# MEMSAndAnalogFrontend.net
KiCad netlist of a schematic drawn in Altium Designer
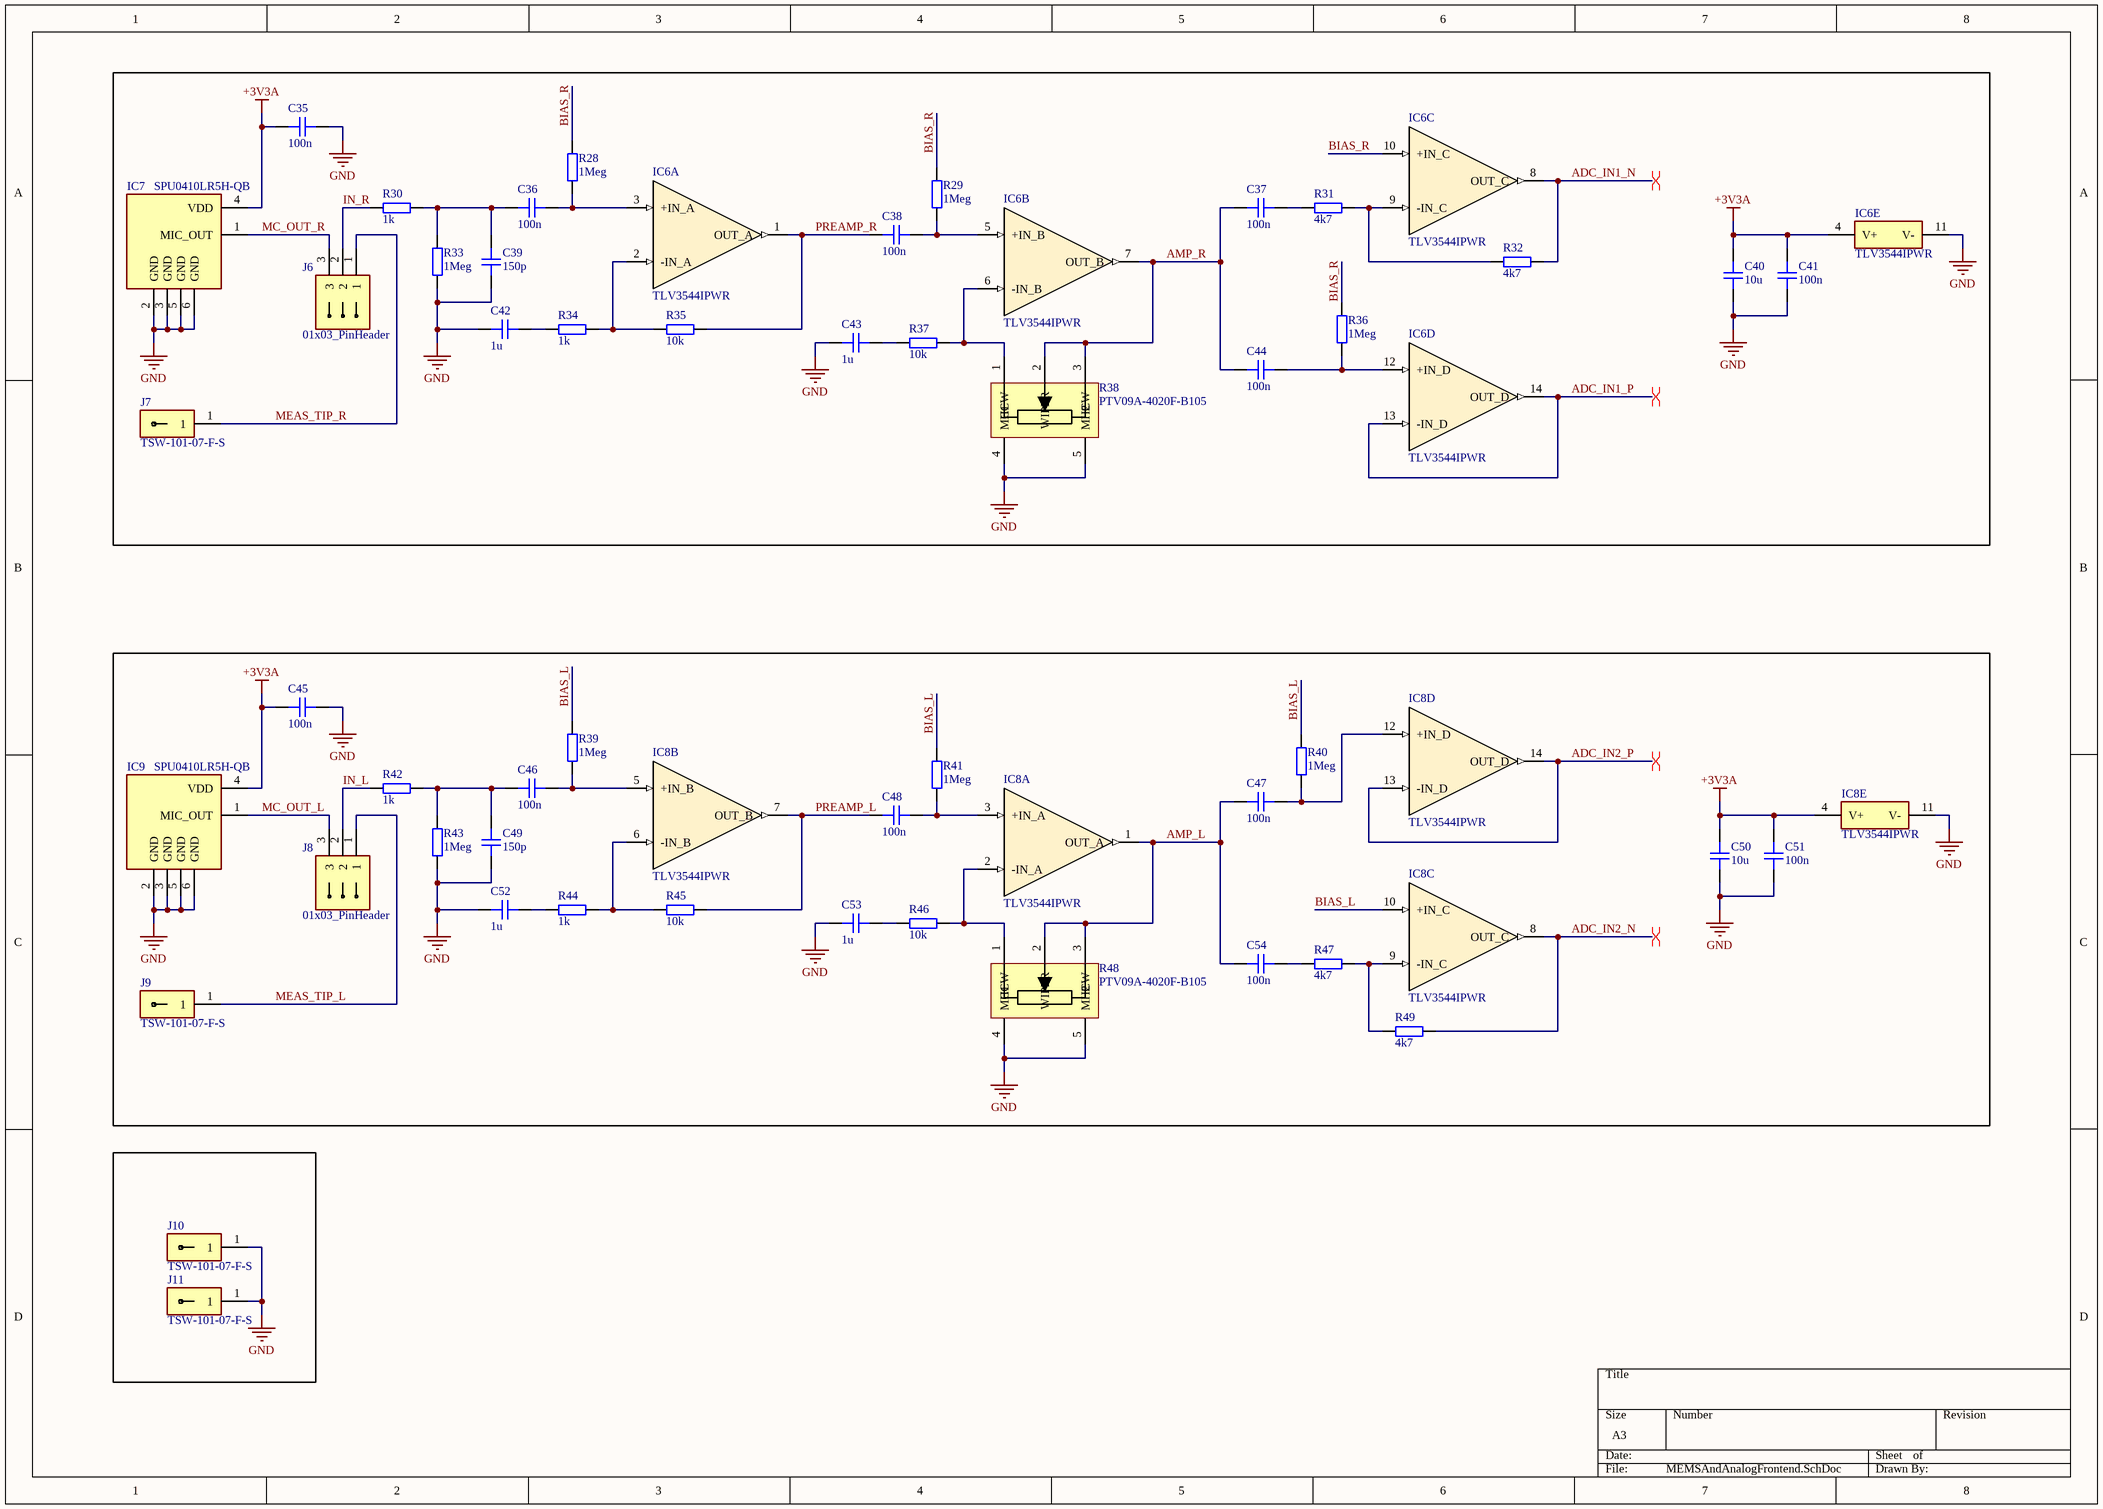
[diagram p0: MEMSAndAnalogFrontend.SchDoc]

(export (version "E")
  (design (tool "Eeschema 10.0.6"))
  (components
    (comp (ref "C35")
      (value "100n")
      (footprint "CAP_0402")
      (description "Capacitor SMD 0402")
      (libsource (lib "Schematic-Lib-PhilsLab") (part "CAP_0402"))
    )
    (comp (ref "C36")
      (value "100n")
      (footprint "CAP_0402")
      (description "Capacitor SMD 0402")
      (libsource (lib "Schematic-Lib-PhilsLab") (part "CAP_0402"))
    )
    (comp (ref "C37")
      (value "100n")
      (footprint "CAP_0402")
      (description "Capacitor SMD 0402")
      (libsource (lib "Schematic-Lib-PhilsLab") (part "CAP_0402"))
    )
    (comp (ref "C38")
      (value "100n")
      (footprint "CAP_0402")
      (description "Capacitor SMD 0402")
      (libsource (lib "Schematic-Lib-PhilsLab") (part "CAP_0402"))
    )
    (comp (ref "C39")
      (value "150p")
      (footprint "CAP_0402")
      (description "Capacitor SMD 0402")
      (libsource (lib "Schematic-Lib-PhilsLab") (part "CAP_0402"))
    )
    (comp (ref "C40")
      (value "10u")
      (footprint "CAP_0603")
      (description "Capacitor SMD 0603")
      (libsource (lib "Schematic-Lib-PhilsLab") (part "CAP_0603"))
    )
    (comp (ref "C41")
      (value "100n")
      (footprint "CAP_0402")
      (description "Capacitor SMD 0402")
      (libsource (lib "Schematic-Lib-PhilsLab") (part "CAP_0402"))
    )
    (comp (ref "C42")
      (value "1u")
      (footprint "CAP_0402")
      (description "Capacitor SMD 0402")
      (libsource (lib "Schematic-Lib-PhilsLab") (part "CAP_0402"))
    )
    (comp (ref "C43")
      (value "1u")
      (footprint "CAP_0402")
      (description "Capacitor SMD 0402")
      (libsource (lib "Schematic-Lib-PhilsLab") (part "CAP_0402"))
    )
    (comp (ref "C44")
      (value "100n")
      (footprint "CAP_0402")
      (description "Capacitor SMD 0402")
      (libsource (lib "Schematic-Lib-PhilsLab") (part "CAP_0402"))
    )
    (comp (ref "C45")
      (value "100n")
      (footprint "CAP_0402")
      (description "Capacitor SMD 0402")
      (libsource (lib "Schematic-Lib-PhilsLab") (part "CAP_0402"))
    )
    (comp (ref "C46")
      (value "100n")
      (footprint "CAP_0402")
      (description "Capacitor SMD 0402")
      (libsource (lib "Schematic-Lib-PhilsLab") (part "CAP_0402"))
    )
    (comp (ref "C47")
      (value "100n")
      (footprint "CAP_0402")
      (description "Capacitor SMD 0402")
      (libsource (lib "Schematic-Lib-PhilsLab") (part "CAP_0402"))
    )
    (comp (ref "C48")
      (value "100n")
      (footprint "CAP_0402")
      (description "Capacitor SMD 0402")
      (libsource (lib "Schematic-Lib-PhilsLab") (part "CAP_0402"))
    )
    (comp (ref "C49")
      (value "150p")
      (footprint "CAP_0402")
      (description "Capacitor SMD 0402")
      (libsource (lib "Schematic-Lib-PhilsLab") (part "CAP_0402"))
    )
    (comp (ref "C50")
      (value "10u")
      (footprint "CAP_0603")
      (description "Capacitor SMD 0603")
      (libsource (lib "Schematic-Lib-PhilsLab") (part "CAP_0603"))
    )
    (comp (ref "C51")
      (value "100n")
      (footprint "CAP_0402")
      (description "Capacitor SMD 0402")
      (libsource (lib "Schematic-Lib-PhilsLab") (part "CAP_0402"))
    )
    (comp (ref "C52")
      (value "1u")
      (footprint "CAP_0402")
      (description "Capacitor SMD 0402")
      (libsource (lib "Schematic-Lib-PhilsLab") (part "CAP_0402"))
    )
    (comp (ref "C53")
      (value "1u")
      (footprint "CAP_0402")
      (description "Capacitor SMD 0402")
      (libsource (lib "Schematic-Lib-PhilsLab") (part "CAP_0402"))
    )
    (comp (ref "C54")
      (value "100n")
      (footprint "CAP_0402")
      (description "Capacitor SMD 0402")
      (libsource (lib "Schematic-Lib-PhilsLab") (part "CAP_0402"))
    )
    (comp (ref "IC6")
      (value "TLV3544IPWR")
      (footprint "BAT_Detector_PCBLib:SOP65P640X120-14N")
      (description "Integrated Circuit")
      (fields (field (name "MOUSER PART NUMBER") "595-TLV3544IPWR"))
      (libsource (lib "BAT_Detector_SCHLib") (part "TLV3544IPWR"))
    )
    (comp (ref "IC7")
      (value "SPU0410LR5H-QB")
      (footprint "SPU0410LR5H-QB")
      (description "Knowles - MEMS Microphones MIC MEMS ANALOG OMNI -38DB")
      (libsource (lib "BAT_Detector_SCHLib") (part "SPU0410LR5H-QB"))
    )
    (comp (ref "IC8")
      (value "TLV3544IPWR")
      (footprint "BAT_Detector_PCBLib:SOP65P640X120-14N")
      (description "Integrated Circuit")
      (fields (field (name "MOUSER PART NUMBER") "595-TLV3544IPWR"))
      (libsource (lib "BAT_Detector_SCHLib") (part "TLV3544IPWR"))
    )
    (comp (ref "IC9")
      (value "SPU0410LR5H-QB")
      (footprint "SPU0410LR5H-QB")
      (description "Knowles - MEMS Microphones MIC MEMS ANALOG OMNI -38DB")
      (libsource (lib "BAT_Detector_SCHLib") (part "SPU0410LR5H-QB"))
    )
    (comp (ref "J6")
      (value "01x03_PinHeader")
      (footprint "BAT_Detector_PCBLib:HDRV3W64P0X254_1X3_732X244X854P")
      (description "Connector")
      (fields
        (field (name "MANUFACTURER_PART_NUMBER") "A2-3PA-2.54DSA(71)")
        (field (name "MOUSER PART NUMBER") "798-A23PA254DSA71")
      )
      (libsource (lib "BAT_Detector_SCHLib") (part "01x03_PinHeader"))
    )
    (comp (ref "J7")
      (value "TSW-101-07-F-S")
      (footprint "BAT_Detector_PCBLib:TSW-101-XX-YY-S")
      (description "Connector")
      (fields (field (name "MOUSER PART NUMBER") "200-TSW10107FS"))
      (libsource (lib "BAT_Detector_SCHLib") (part "TSW-101-07-F-S"))
    )
    (comp (ref "J8")
      (value "01x03_PinHeader")
      (footprint "BAT_Detector_PCBLib:HDRV3W64P0X254_1X3_732X244X854P")
      (description "Connector")
      (fields
        (field (name "MANUFACTURER_PART_NUMBER") "A2-3PA-2.54DSA(71)")
        (field (name "MOUSER PART NUMBER") "798-A23PA254DSA71")
      )
      (libsource (lib "BAT_Detector_SCHLib") (part "01x03_PinHeader"))
    )
    (comp (ref "J9")
      (value "TSW-101-07-F-S")
      (footprint "BAT_Detector_PCBLib:TSW-101-XX-YY-S")
      (description "Connector")
      (fields (field (name "MOUSER PART NUMBER") "200-TSW10107FS"))
      (libsource (lib "BAT_Detector_SCHLib") (part "TSW-101-07-F-S"))
    )
    (comp (ref "J10")
      (value "TSW-101-07-F-S")
      (footprint "BAT_Detector_PCBLib:TSW-101-XX-YY-S")
      (description "Connector")
      (fields (field (name "MOUSER PART NUMBER") "200-TSW10107FS"))
      (libsource (lib "BAT_Detector_SCHLib") (part "TSW-101-07-F-S"))
    )
    (comp (ref "J11")
      (value "TSW-101-07-F-S")
      (footprint "BAT_Detector_PCBLib:TSW-101-XX-YY-S")
      (description "Connector")
      (fields (field (name "MOUSER PART NUMBER") "200-TSW10107FS"))
      (libsource (lib "BAT_Detector_SCHLib") (part "TSW-101-07-F-S"))
    )
    (comp (ref "R28")
      (value "1Meg")
      (footprint "RES_0402")
      (description "Resistor SMD 0402")
      (libsource (lib "Schematic-Lib-PhilsLab") (part "RES_0402"))
    )
    (comp (ref "R29")
      (value "1Meg")
      (footprint "RES_0402")
      (description "Resistor SMD 0402")
      (libsource (lib "Schematic-Lib-PhilsLab") (part "RES_0402"))
    )
    (comp (ref "R30")
      (value "1k")
      (footprint "RES_0402")
      (description "Resistor SMD 0402")
      (libsource (lib "Schematic-Lib-PhilsLab") (part "RES_0402"))
    )
    (comp (ref "R31")
      (value "4k7")
      (footprint "RES_0402")
      (description "Resistor SMD 0402")
      (libsource (lib "Schematic-Lib-PhilsLab") (part "RES_0402"))
    )
    (comp (ref "R32")
      (value "4k7")
      (footprint "RES_0402")
      (description "Resistor SMD 0402")
      (libsource (lib "Schematic-Lib-PhilsLab") (part "RES_0402"))
    )
    (comp (ref "R33")
      (value "1Meg")
      (footprint "RES_0402")
      (description "Resistor SMD 0402")
      (libsource (lib "Schematic-Lib-PhilsLab") (part "RES_0402"))
    )
    (comp (ref "R34")
      (value "1k")
      (footprint "RES_0402")
      (description "Resistor SMD 0402")
      (libsource (lib "Schematic-Lib-PhilsLab") (part "RES_0402"))
    )
    (comp (ref "R35")
      (value "10k")
      (footprint "RES_0402")
      (description "Resistor SMD 0402")
      (libsource (lib "Schematic-Lib-PhilsLab") (part "RES_0402"))
    )
    (comp (ref "R36")
      (value "1Meg")
      (footprint "RES_0402")
      (description "Resistor SMD 0402")
      (libsource (lib "Schematic-Lib-PhilsLab") (part "RES_0402"))
    )
    (comp (ref "R37")
      (value "10k")
      (footprint "RES_0402")
      (description "Resistor SMD 0402")
      (libsource (lib "Schematic-Lib-PhilsLab") (part "RES_0402"))
    )
    (comp (ref "R38")
      (value "PTV09A-4020F-B105")
      (footprint "BAT_Detector_PCBLib:PTV09A4020FB103")
      (description "Variable Resistor")
      (fields (field (name "MOUSER PART NUMBER") "652-PTV09A4020FB105"))
      (libsource (lib "BAT_Detector_SCHLib") (part "PTV09A-4020F-B105"))
    )
    (comp (ref "R39")
      (value "1Meg")
      (footprint "RES_0402")
      (description "Resistor SMD 0402")
      (libsource (lib "Schematic-Lib-PhilsLab") (part "RES_0402"))
    )
    (comp (ref "R40")
      (value "1Meg")
      (footprint "RES_0402")
      (description "Resistor SMD 0402")
      (libsource (lib "Schematic-Lib-PhilsLab") (part "RES_0402"))
    )
    (comp (ref "R41")
      (value "1Meg")
      (footprint "RES_0402")
      (description "Resistor SMD 0402")
      (libsource (lib "Schematic-Lib-PhilsLab") (part "RES_0402"))
    )
    (comp (ref "R42")
      (value "1k")
      (footprint "RES_0402")
      (description "Resistor SMD 0402")
      (libsource (lib "Schematic-Lib-PhilsLab") (part "RES_0402"))
    )
    (comp (ref "R43")
      (value "1Meg")
      (footprint "RES_0402")
      (description "Resistor SMD 0402")
      (libsource (lib "Schematic-Lib-PhilsLab") (part "RES_0402"))
    )
    (comp (ref "R44")
      (value "1k")
      (footprint "RES_0402")
      (description "Resistor SMD 0402")
      (libsource (lib "Schematic-Lib-PhilsLab") (part "RES_0402"))
    )
    (comp (ref "R45")
      (value "10k")
      (footprint "RES_0402")
      (description "Resistor SMD 0402")
      (libsource (lib "Schematic-Lib-PhilsLab") (part "RES_0402"))
    )
    (comp (ref "R46")
      (value "10k")
      (footprint "RES_0402")
      (description "Resistor SMD 0402")
      (libsource (lib "Schematic-Lib-PhilsLab") (part "RES_0402"))
    )
    (comp (ref "R47")
      (value "4k7")
      (footprint "RES_0402")
      (description "Resistor SMD 0402")
      (libsource (lib "Schematic-Lib-PhilsLab") (part "RES_0402"))
    )
    (comp (ref "R48")
      (value "PTV09A-4020F-B105")
      (footprint "BAT_Detector_PCBLib:PTV09A4020FB103")
      (description "Variable Resistor")
      (fields (field (name "MOUSER PART NUMBER") "652-PTV09A4020FB105"))
      (libsource (lib "BAT_Detector_SCHLib") (part "PTV09A-4020F-B105"))
    )
    (comp (ref "R49")
      (value "4k7")
      (footprint "RES_0402")
      (description "Resistor SMD 0402")
      (libsource (lib "Schematic-Lib-PhilsLab") (part "RES_0402"))
    )
  )
  (nets
    (net (code "1") (name "+3V3A") (class "Default")
      (node (ref "C35") (pin "1") (pinfunction "1_1") (pintype "passive"))
      (node (ref "C40") (pin "2") (pinfunction "2_2") (pintype "passive"))
      (node (ref "C41") (pin "2") (pinfunction "2_2") (pintype "passive"))
      (node (ref "C45") (pin "1") (pinfunction "1_1") (pintype "passive"))
      (node (ref "C50") (pin "2") (pinfunction "2_2") (pintype "passive"))
      (node (ref "C51") (pin "2") (pinfunction "2_2") (pintype "passive"))
      (node (ref "IC6") (pin "4") (pinfunction "V+_4") (pintype "power_in"))
      (node (ref "IC7") (pin "4") (pinfunction "VDD_4") (pintype "passive"))
      (node (ref "IC8") (pin "4") (pinfunction "V+_4") (pintype "power_in"))
      (node (ref "IC9") (pin "4") (pinfunction "VDD_4") (pintype "passive"))
    )
    (net (code "2") (name "/ADC_IN1_N") (class "Default")
      (node (ref "IC6") (pin "8") (pinfunction "OUT_C_8") (pintype "output"))
      (node (ref "R32") (pin "2") (pinfunction "2_2") (pintype "passive"))
    )
    (net (code "3") (name "/ADC_IN1_P") (class "Default")
      (node (ref "IC6") (pin "13") (pinfunction "-IN_D_13") (pintype "input"))
      (node (ref "IC6") (pin "14") (pinfunction "OUT_D_14") (pintype "output"))
    )
    (net (code "4") (name "/ADC_IN2_N") (class "Default")
      (node (ref "IC8") (pin "8") (pinfunction "OUT_C_8") (pintype "output"))
      (node (ref "R49") (pin "2") (pinfunction "2_2") (pintype "passive"))
    )
    (net (code "5") (name "/ADC_IN2_P") (class "Default")
      (node (ref "IC8") (pin "13") (pinfunction "-IN_D_13") (pintype "input"))
      (node (ref "IC8") (pin "14") (pinfunction "OUT_D_14") (pintype "output"))
    )
    (net (code "6") (name "/AMP_L") (class "Default")
      (node (ref "C47") (pin "2") (pinfunction "2_2") (pintype "passive"))
      (node (ref "C54") (pin "2") (pinfunction "2_2") (pintype "passive"))
      (node (ref "IC8") (pin "1") (pinfunction "OUT_A_1") (pintype "output"))
      (node (ref "R48") (pin "2") (pinfunction "WIPER_2") (pintype "passive"))
      (node (ref "R48") (pin "3") (pinfunction "CW_3") (pintype "passive"))
    )
    (net (code "7") (name "/AMP_R") (class "Default")
      (node (ref "C37") (pin "2") (pinfunction "2_2") (pintype "passive"))
      (node (ref "C44") (pin "2") (pinfunction "2_2") (pintype "passive"))
      (node (ref "IC6") (pin "7") (pinfunction "OUT_B_7") (pintype "output"))
      (node (ref "R38") (pin "2") (pinfunction "WIPER_2") (pintype "passive"))
      (node (ref "R38") (pin "3") (pinfunction "CW_3") (pintype "passive"))
    )
    (net (code "8") (name "/BIAS_L") (class "Default")
      (node (ref "IC8") (pin "10") (pinfunction "+IN_C_10") (pintype "input"))
      (node (ref "R39") (pin "2") (pinfunction "2_2") (pintype "passive"))
      (node (ref "R40") (pin "2") (pinfunction "2_2") (pintype "passive"))
      (node (ref "R41") (pin "2") (pinfunction "2_2") (pintype "passive"))
    )
    (net (code "9") (name "/BIAS_R") (class "Default")
      (node (ref "IC6") (pin "10") (pinfunction "+IN_C_10") (pintype "input"))
      (node (ref "R28") (pin "2") (pinfunction "2_2") (pintype "passive"))
      (node (ref "R29") (pin "2") (pinfunction "2_2") (pintype "passive"))
      (node (ref "R36") (pin "2") (pinfunction "2_2") (pintype "passive"))
    )
    (net (code "10") (name "/IN_L") (class "Default")
      (node (ref "J8") (pin "2") (pinfunction "2_2") (pintype "passive"))
      (node (ref "R42") (pin "1") (pinfunction "1_1") (pintype "passive"))
    )
    (net (code "11") (name "/IN_R") (class "Default")
      (node (ref "J6") (pin "2") (pinfunction "2_2") (pintype "passive"))
      (node (ref "R30") (pin "1") (pinfunction "1_1") (pintype "passive"))
    )
    (net (code "12") (name "/MC_OUT_L") (class "Default")
      (node (ref "IC9") (pin "1") (pinfunction "MIC_OUT_1") (pintype "passive"))
      (node (ref "J8") (pin "3") (pinfunction "3_3") (pintype "passive"))
    )
    (net (code "13") (name "/MC_OUT_R") (class "Default")
      (node (ref "IC7") (pin "1") (pinfunction "MIC_OUT_1") (pintype "passive"))
      (node (ref "J6") (pin "3") (pinfunction "3_3") (pintype "passive"))
    )
    (net (code "14") (name "/MEAS_TIP_L") (class "Default")
      (node (ref "J8") (pin "1") (pinfunction "1_1") (pintype "passive"))
      (node (ref "J9") (pin "1") (pinfunction "1_1") (pintype "passive"))
    )
    (net (code "15") (name "/MEAS_TIP_R") (class "Default")
      (node (ref "J6") (pin "1") (pinfunction "1_1") (pintype "passive"))
      (node (ref "J7") (pin "1") (pinfunction "1_1") (pintype "passive"))
    )
    (net (code "16") (name "/PREAMP_L") (class "Default")
      (node (ref "C48") (pin "2") (pinfunction "2_2") (pintype "passive"))
      (node (ref "IC8") (pin "7") (pinfunction "OUT_B_7") (pintype "output"))
      (node (ref "R45") (pin "2") (pinfunction "2_2") (pintype "passive"))
    )
    (net (code "17") (name "/PREAMP_R") (class "Default")
      (node (ref "C38") (pin "2") (pinfunction "2_2") (pintype "passive"))
      (node (ref "IC6") (pin "1") (pinfunction "OUT_A_1") (pintype "output"))
      (node (ref "R35") (pin "2") (pinfunction "2_2") (pintype "passive"))
    )
    (net (code "18") (name "GND") (class "Default")
      (node (ref "C35") (pin "2") (pinfunction "2_2") (pintype "passive"))
      (node (ref "C39") (pin "2") (pinfunction "2_2") (pintype "passive"))
      (node (ref "C40") (pin "1") (pinfunction "1_1") (pintype "passive"))
      (node (ref "C41") (pin "1") (pinfunction "1_1") (pintype "passive"))
      (node (ref "C42") (pin "1") (pinfunction "1_1") (pintype "passive"))
      (node (ref "C43") (pin "1") (pinfunction "1_1") (pintype "passive"))
      (node (ref "C45") (pin "2") (pinfunction "2_2") (pintype "passive"))
      (node (ref "C49") (pin "2") (pinfunction "2_2") (pintype "passive"))
      (node (ref "C50") (pin "1") (pinfunction "1_1") (pintype "passive"))
      (node (ref "C51") (pin "1") (pinfunction "1_1") (pintype "passive"))
      (node (ref "C52") (pin "1") (pinfunction "1_1") (pintype "passive"))
      (node (ref "C53") (pin "1") (pinfunction "1_1") (pintype "passive"))
      (node (ref "IC6") (pin "11") (pinfunction "V-_11") (pintype "power_in"))
      (node (ref "IC7") (pin "2") (pinfunction "GND_2") (pintype "passive"))
      (node (ref "IC7") (pin "3") (pinfunction "GND_3") (pintype "passive"))
      (node (ref "IC7") (pin "5") (pinfunction "GND_5") (pintype "passive"))
      (node (ref "IC7") (pin "6") (pinfunction "GND_6") (pintype "passive"))
      (node (ref "IC8") (pin "11") (pinfunction "V-_11") (pintype "power_in"))
      (node (ref "IC9") (pin "2") (pinfunction "GND_2") (pintype "passive"))
      (node (ref "IC9") (pin "3") (pinfunction "GND_3") (pintype "passive"))
      (node (ref "IC9") (pin "5") (pinfunction "GND_5") (pintype "passive"))
      (node (ref "IC9") (pin "6") (pinfunction "GND_6") (pintype "passive"))
      (node (ref "J10") (pin "1") (pinfunction "1_1") (pintype "passive"))
      (node (ref "J11") (pin "1") (pinfunction "1_1") (pintype "passive"))
      (node (ref "R33") (pin "1") (pinfunction "1_1") (pintype "passive"))
      (node (ref "R38") (pin "4") (pinfunction "MH1_4") (pintype "passive"))
      (node (ref "R38") (pin "5") (pinfunction "MH2_5") (pintype "passive"))
      (node (ref "R43") (pin "1") (pinfunction "1_1") (pintype "passive"))
      (node (ref "R48") (pin "4") (pinfunction "MH1_4") (pintype "passive"))
      (node (ref "R48") (pin "5") (pinfunction "MH2_5") (pintype "passive"))
    )
    (net (code "19") (name "Net-(C36-Pad2)") (class "Default")
      (node (ref "C36") (pin "2") (pinfunction "2_2") (pintype "passive"))
      (node (ref "C39") (pin "1") (pinfunction "1_1") (pintype "passive"))
      (node (ref "R30") (pin "2") (pinfunction "2_2") (pintype "passive"))
      (node (ref "R33") (pin "2") (pinfunction "2_2") (pintype "passive"))
    )
    (net (code "20") (name "Net-(C37-Pad1)") (class "Default")
      (node (ref "C37") (pin "1") (pinfunction "1_1") (pintype "passive"))
      (node (ref "R31") (pin "1") (pinfunction "1_1") (pintype "passive"))
    )
    (net (code "21") (name "Net-(C42-Pad2)") (class "Default")
      (node (ref "C42") (pin "2") (pinfunction "2_2") (pintype "passive"))
      (node (ref "R34") (pin "1") (pinfunction "1_1") (pintype "passive"))
    )
    (net (code "22") (name "Net-(C43-Pad2)") (class "Default")
      (node (ref "C43") (pin "2") (pinfunction "2_2") (pintype "passive"))
      (node (ref "R37") (pin "1") (pinfunction "1_1") (pintype "passive"))
    )
    (net (code "23") (name "Net-(C46-Pad2)") (class "Default")
      (node (ref "C46") (pin "2") (pinfunction "2_2") (pintype "passive"))
      (node (ref "C49") (pin "1") (pinfunction "1_1") (pintype "passive"))
      (node (ref "R42") (pin "2") (pinfunction "2_2") (pintype "passive"))
      (node (ref "R43") (pin "2") (pinfunction "2_2") (pintype "passive"))
    )
    (net (code "24") (name "Net-(C52-Pad2)") (class "Default")
      (node (ref "C52") (pin "2") (pinfunction "2_2") (pintype "passive"))
      (node (ref "R44") (pin "1") (pinfunction "1_1") (pintype "passive"))
    )
    (net (code "25") (name "Net-(C53-Pad2)") (class "Default")
      (node (ref "C53") (pin "2") (pinfunction "2_2") (pintype "passive"))
      (node (ref "R46") (pin "1") (pinfunction "1_1") (pintype "passive"))
    )
    (net (code "26") (name "Net-(C54-Pad1)") (class "Default")
      (node (ref "C54") (pin "1") (pinfunction "1_1") (pintype "passive"))
      (node (ref "R47") (pin "1") (pinfunction "1_1") (pintype "passive"))
    )
    (net (code "27") (name "Net-(IC6A-+IN_A)") (class "Default")
      (node (ref "C36") (pin "1") (pinfunction "1_1") (pintype "passive"))
      (node (ref "IC6") (pin "3") (pinfunction "+IN_A_3") (pintype "input"))
      (node (ref "R28") (pin "1") (pinfunction "1_1") (pintype "passive"))
    )
    (net (code "28") (name "Net-(IC6A--IN_A)") (class "Default")
      (node (ref "IC6") (pin "2") (pinfunction "-IN_A_2") (pintype "input"))
      (node (ref "R34") (pin "2") (pinfunction "2_2") (pintype "passive"))
      (node (ref "R35") (pin "1") (pinfunction "1_1") (pintype "passive"))
    )
    (net (code "29") (name "Net-(IC6B-+IN_B)") (class "Default")
      (node (ref "C38") (pin "1") (pinfunction "1_1") (pintype "passive"))
      (node (ref "IC6") (pin "5") (pinfunction "+IN_B_5") (pintype "input"))
      (node (ref "R29") (pin "1") (pinfunction "1_1") (pintype "passive"))
    )
    (net (code "30") (name "Net-(IC6B--IN_B)") (class "Default")
      (node (ref "IC6") (pin "6") (pinfunction "-IN_B_6") (pintype "input"))
      (node (ref "R37") (pin "2") (pinfunction "2_2") (pintype "passive"))
      (node (ref "R38") (pin "1") (pinfunction "CCW_1") (pintype "passive"))
    )
    (net (code "31") (name "Net-(IC6C--IN_C)") (class "Default")
      (node (ref "IC6") (pin "9") (pinfunction "-IN_C_9") (pintype "input"))
      (node (ref "R31") (pin "2") (pinfunction "2_2") (pintype "passive"))
      (node (ref "R32") (pin "1") (pinfunction "1_1") (pintype "passive"))
    )
    (net (code "32") (name "Net-(IC6D-+IN_D)") (class "Default")
      (node (ref "C44") (pin "1") (pinfunction "1_1") (pintype "passive"))
      (node (ref "IC6") (pin "12") (pinfunction "+IN_D_12") (pintype "input"))
      (node (ref "R36") (pin "1") (pinfunction "1_1") (pintype "passive"))
    )
    (net (code "33") (name "Net-(IC8A-+IN_A)") (class "Default")
      (node (ref "C48") (pin "1") (pinfunction "1_1") (pintype "passive"))
      (node (ref "IC8") (pin "3") (pinfunction "+IN_A_3") (pintype "input"))
      (node (ref "R41") (pin "1") (pinfunction "1_1") (pintype "passive"))
    )
    (net (code "34") (name "Net-(IC8A--IN_A)") (class "Default")
      (node (ref "IC8") (pin "2") (pinfunction "-IN_A_2") (pintype "input"))
      (node (ref "R46") (pin "2") (pinfunction "2_2") (pintype "passive"))
      (node (ref "R48") (pin "1") (pinfunction "CCW_1") (pintype "passive"))
    )
    (net (code "35") (name "Net-(IC8B-+IN_B)") (class "Default")
      (node (ref "C46") (pin "1") (pinfunction "1_1") (pintype "passive"))
      (node (ref "IC8") (pin "5") (pinfunction "+IN_B_5") (pintype "input"))
      (node (ref "R39") (pin "1") (pinfunction "1_1") (pintype "passive"))
    )
    (net (code "36") (name "Net-(IC8B--IN_B)") (class "Default")
      (node (ref "IC8") (pin "6") (pinfunction "-IN_B_6") (pintype "input"))
      (node (ref "R44") (pin "2") (pinfunction "2_2") (pintype "passive"))
      (node (ref "R45") (pin "1") (pinfunction "1_1") (pintype "passive"))
    )
    (net (code "37") (name "Net-(IC8C--IN_C)") (class "Default")
      (node (ref "IC8") (pin "9") (pinfunction "-IN_C_9") (pintype "input"))
      (node (ref "R47") (pin "2") (pinfunction "2_2") (pintype "passive"))
      (node (ref "R49") (pin "1") (pinfunction "1_1") (pintype "passive"))
    )
    (net (code "38") (name "Net-(IC8D-+IN_D)") (class "Default")
      (node (ref "C47") (pin "1") (pinfunction "1_1") (pintype "passive"))
      (node (ref "IC8") (pin "12") (pinfunction "+IN_D_12") (pintype "input"))
      (node (ref "R40") (pin "1") (pinfunction "1_1") (pintype "passive"))
    )
  )
)
